# GPS.net
KiCad netlist of a schematic drawn in Altium Designer
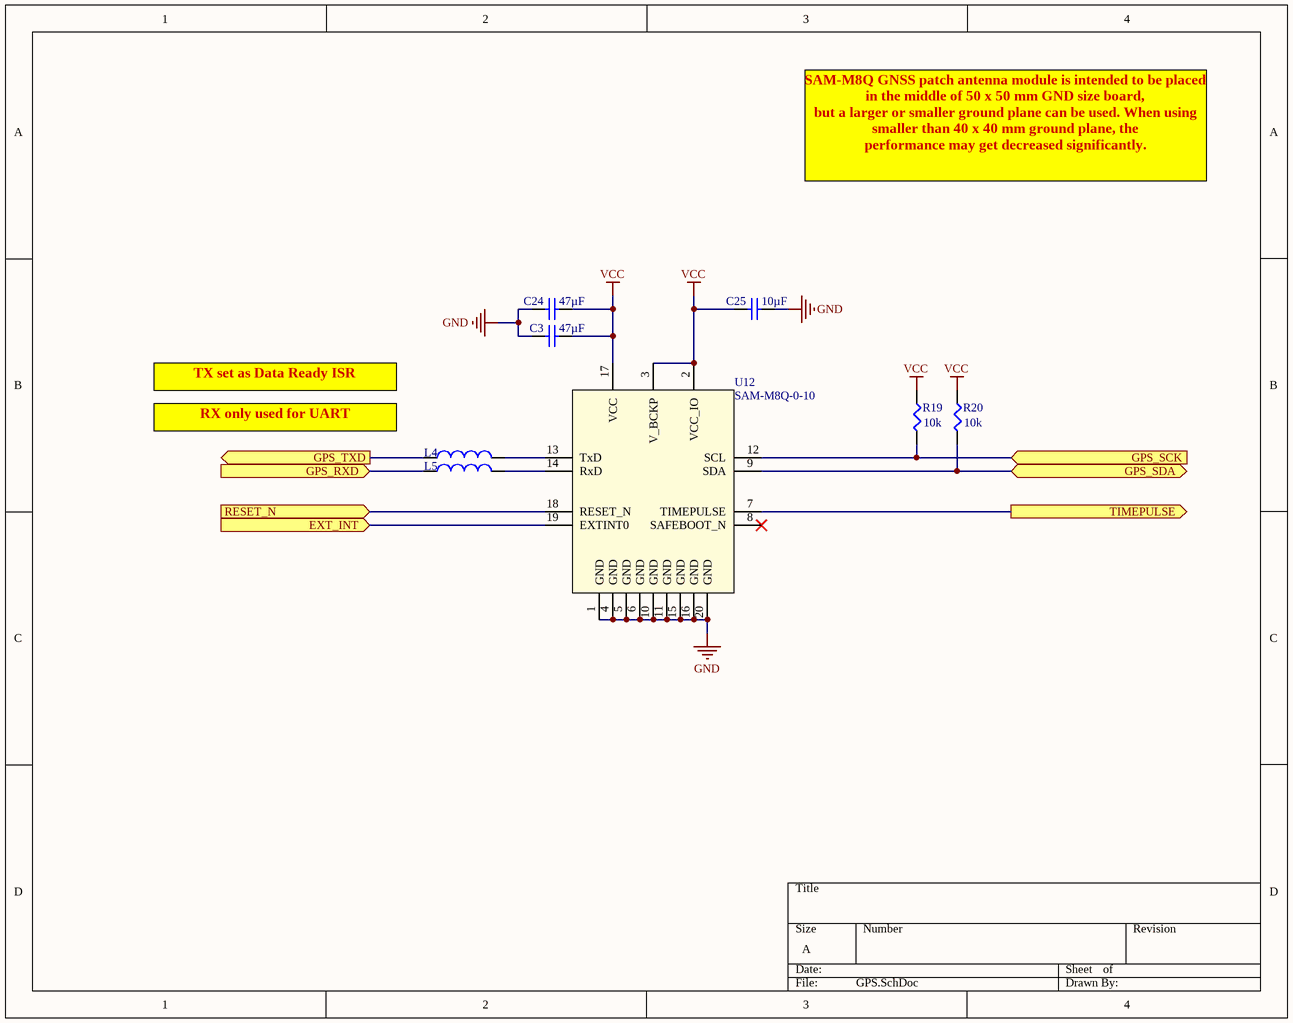
[diagram p0: GPS.SchDoc]

(export (version "E")
  (design (tool "Eeschema 10.0.6"))
  (components
    (comp (ref "C3")
      (value "CL21A476MQCLRNC")
      (footprint "C0603N")
      (fields
        (field (name "HOUSEPART") "NO")
        (field (name "TOLERANCE") "±20%")
        (field (name "VOLTAGE") "6.3V")
        (field (name "CAPACITANCE") "47µF")
      )
      (libsource (lib "MF_Passives") (part "CAPACITOR_NP"))
    )
    (comp (ref "C24")
      (value "CL21A476MQCLRNC")
      (footprint "C0603N")
      (fields
        (field (name "HOUSEPART") "NO")
        (field (name "TOLERANCE") "±20%")
        (field (name "VOLTAGE") "6.3V")
        (field (name "CAPACITANCE") "47µF")
      )
      (libsource (lib "MF_Passives") (part "CAPACITOR_NP"))
    )
    (comp (ref "C25")
      (value "C1608X5R1A106K080AC")
      (footprint "C0603N")
      (description "4.7µF ±10% 10V Ceramic Capacitor X5R 0603")
      (fields
        (field (name "HOUSEPART") "NO")
        (field (name "TOLERANCE") "±10%")
        (field (name "CAPACITANCE") "10µF")
      )
      (libsource (lib "MF_Passives") (part "CAPACITOR_NP"))
    )
    (comp (ref "L4")
      (value "LI0603G221R-10")
      (footprint "R0603L")
      (fields (field (name "HOUSEPART") "NO"))
      (libsource (lib "MF_Passives") (part "INDUCTOR"))
    )
    (comp (ref "L5")
      (value "LI0603G221R-10")
      (footprint "R0603L")
      (fields (field (name "HOUSEPART") "NO"))
      (libsource (lib "MF_Passives") (part "INDUCTOR"))
    )
    (comp (ref "R19")
      (value "10k")
      (footprint "SMD-0603-RES")
      (description "RES SMD 10K OHM 1% 1/10W 0603")
      (fields
        (field (name "PART NUMBER") "ERJ-3EKF1002V")
        (field (name "DIGI-KEY PART NUMBER") "P10.0KHCT-ND")
      )
      (libsource (lib "Panasonic_ERJ_0603") (part "ERJ-3EKF1002V"))
    )
    (comp (ref "R20")
      (value "10k")
      (footprint "SMD-0603-RES")
      (description "RES SMD 10K OHM 1% 1/10W 0603")
      (fields
        (field (name "PART NUMBER") "ERJ-3EKF1002V")
        (field (name "DIGI-KEY PART NUMBER") "P10.0KHCT-ND")
      )
      (libsource (lib "Panasonic_ERJ_0603") (part "ERJ-3EKF1002V"))
    )
    (comp (ref "U12")
      (value "SAM-M8Q-0-10")
      (footprint "SAM-M8Q")
      (description "u-Blox M8 Gnss Antenna Module Tc")
      (libsource (lib "ublox") (part "ublox-sam-m8Q"))
    )
  )
  (nets
    (net (code "1") (name "/EXT_INT") (class "Default")
      (node (ref "U12") (pin "19") (pinfunction "EXTINT0_19") (pintype "passive"))
    )
    (net (code "2") (name "/GPS_RXD") (class "Default")
      (node (ref "L5") (pin "1") (pinfunction "1_1") (pintype "passive"))
    )
    (net (code "3") (name "/GPS_SCK") (class "Default")
      (node (ref "R19") (pin "2") (pinfunction "2_2") (pintype "passive"))
      (node (ref "U12") (pin "12") (pinfunction "SCL_12") (pintype "passive"))
    )
    (net (code "4") (name "/GPS_SDA") (class "Default")
      (node (ref "R20") (pin "2") (pinfunction "2_2") (pintype "passive"))
      (node (ref "U12") (pin "9") (pinfunction "SDA_9") (pintype "passive"))
    )
    (net (code "5") (name "/GPS_TXD") (class "Default")
      (node (ref "L4") (pin "1") (pinfunction "1_1") (pintype "passive"))
    )
    (net (code "6") (name "/RESET_N") (class "Default")
      (node (ref "U12") (pin "18") (pinfunction "RESET_N_18") (pintype "passive"))
    )
    (net (code "7") (name "/TIMEPULSE") (class "Default")
      (node (ref "U12") (pin "7") (pinfunction "TIMEPULSE_7") (pintype "passive"))
    )
    (net (code "8") (name "GND") (class "Default")
      (node (ref "C24") (pin "1") (pinfunction "1_1") (pintype "passive"))
      (node (ref "C25") (pin "2") (pinfunction "2_2") (pintype "passive"))
      (node (ref "C3") (pin "1") (pinfunction "1_1") (pintype "passive"))
      (node (ref "U12") (pin "1") (pinfunction "GND_1") (pintype "passive"))
      (node (ref "U12") (pin "10") (pinfunction "GND_10") (pintype "passive"))
      (node (ref "U12") (pin "11") (pinfunction "GND_11") (pintype "passive"))
      (node (ref "U12") (pin "15") (pinfunction "GND_15") (pintype "passive"))
      (node (ref "U12") (pin "16") (pinfunction "GND_16") (pintype "passive"))
      (node (ref "U12") (pin "20") (pinfunction "GND_20") (pintype "passive"))
      (node (ref "U12") (pin "4") (pinfunction "GND_4") (pintype "passive"))
      (node (ref "U12") (pin "5") (pinfunction "GND_5") (pintype "passive"))
      (node (ref "U12") (pin "6") (pinfunction "GND_6") (pintype "passive"))
    )
    (net (code "9") (name "Net-(U12-RxD)") (class "Default")
      (node (ref "L5") (pin "2") (pinfunction "2_2") (pintype "passive"))
      (node (ref "U12") (pin "14") (pinfunction "RxD_14") (pintype "passive"))
    )
    (net (code "10") (name "Net-(U12-TxD)") (class "Default")
      (node (ref "L4") (pin "2") (pinfunction "2_2") (pintype "passive"))
      (node (ref "U12") (pin "13") (pinfunction "TxD_13") (pintype "passive"))
    )
    (net (code "11") (name "VCC") (class "Default")
      (node (ref "C24") (pin "2") (pinfunction "2_2") (pintype "passive"))
      (node (ref "C25") (pin "1") (pinfunction "1_1") (pintype "passive"))
      (node (ref "C3") (pin "2") (pinfunction "2_2") (pintype "passive"))
      (node (ref "R19") (pin "1") (pinfunction "1_1") (pintype "passive"))
      (node (ref "R20") (pin "1") (pinfunction "1_1") (pintype "passive"))
      (node (ref "U12") (pin "17") (pinfunction "VCC_17") (pintype "passive"))
      (node (ref "U12") (pin "2") (pinfunction "VCC_IO_2") (pintype "passive"))
      (node (ref "U12") (pin "3") (pinfunction "V_BCKP_3") (pintype "passive"))
    )
    (net (code "12") (name "unconnected-(U12-SAFEBOOT_N-Pad8)") (class "Default")
      (node (ref "U12") (pin "8") (pinfunction "SAFEBOOT_N_8") (pintype "passive+no_connect"))
    )
  )
)
